# Sheet1.net
KiCad netlist of a schematic drawn in Altium Designer
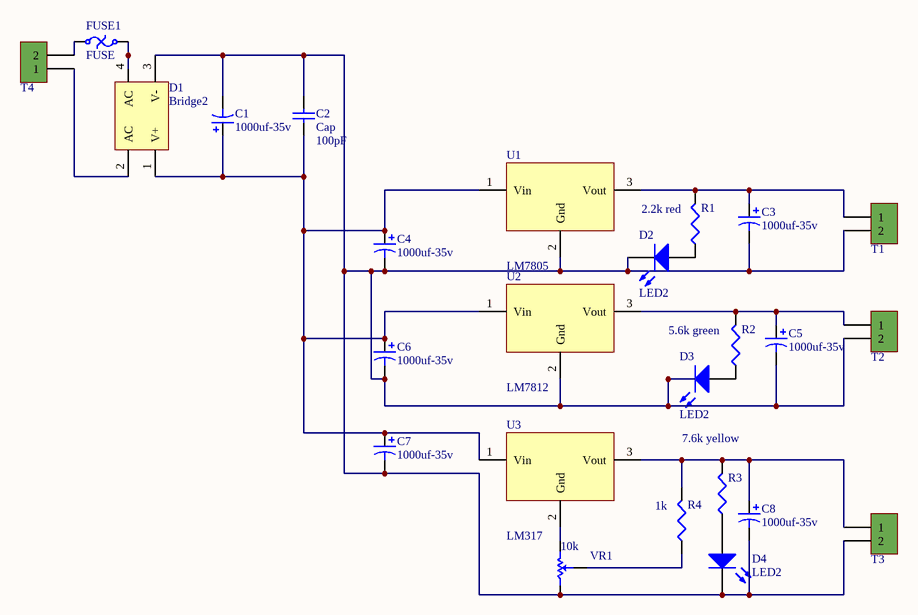
[diagram p0: Sheet1.SchDoc]

(export (version "E")
  (design (tool "Eeschema 10.0.6"))
  (components
    (comp (ref "C1")
      (value "1000uf-35v")
      (footprint "RB7.6-15")
      (description "Polarized Capacitor (Radial)")
      (fields (field (name "PUBLISHER") "Altium Limited"))
      (libsource (lib "Miscellaneous Devices") (part "Cap Pol1"))
    )
    (comp (ref "C2")
      (value "Cap")
      (footprint "RAD-0.3")
      (description "Capacitor")
      (fields (field (name "ALTIUM_VALUE") "100pF") (field (name "PUBLISHER") "Altium Limited"))
      (libsource (lib "Miscellaneous Devices") (part "Cap"))
    )
    (comp (ref "C3")
      (value "1000uf-35v")
      (footprint "RB7.6-15")
      (description "Polarized Capacitor (Radial)")
      (fields (field (name "PUBLISHER") "Altium Limited"))
      (libsource (lib "Miscellaneous Devices") (part "Cap Pol1"))
    )
    (comp (ref "C4")
      (value "1000uf-35v")
      (footprint "RB7.6-15")
      (description "Polarized Capacitor (Radial)")
      (fields (field (name "PUBLISHER") "Altium Limited"))
      (libsource (lib "Miscellaneous Devices") (part "Cap Pol1"))
    )
    (comp (ref "C5")
      (value "1000uf-35v")
      (footprint "RB7.6-15")
      (description "Polarized Capacitor (Radial)")
      (fields (field (name "PUBLISHER") "Altium Limited"))
      (libsource (lib "Miscellaneous Devices") (part "Cap Pol1"))
    )
    (comp (ref "C6")
      (value "1000uf-35v")
      (footprint "RB7.6-15")
      (description "Polarized Capacitor (Radial)")
      (fields (field (name "PUBLISHER") "Altium Limited"))
      (libsource (lib "Miscellaneous Devices") (part "Cap Pol1"))
    )
    (comp (ref "C7")
      (value "1000uf-35v")
      (footprint "RB7.6-15")
      (description "Polarized Capacitor (Radial)")
      (fields (field (name "PUBLISHER") "Altium Limited"))
      (libsource (lib "Miscellaneous Devices") (part "Cap Pol1"))
    )
    (comp (ref "C8")
      (value "1000uf-35v")
      (footprint "RB7.6-15")
      (description "Polarized Capacitor (Radial)")
      (fields (field (name "PUBLISHER") "Altium Limited"))
      (libsource (lib "Miscellaneous Devices") (part "Cap Pol1"))
    )
    (comp (ref "D1")
      (value "Bridge2")
      (footprint "D-46_6A")
      (description "Diode Bridge")
      (fields (field (name "PUBLISHER") "Altium Limited"))
      (libsource (lib "Miscellaneous Devices") (part "Bridge2"))
    )
    (comp (ref "D2")
      (value "LED2")
      (footprint "3.2X1.6X1.1")
      (description "Typical RED, GREEN, YELLOW, AMBER GaAs LED")
      (fields (field (name "PUBLISHER") "Altium Limited"))
      (libsource (lib "Miscellaneous Devices") (part "LED2"))
    )
    (comp (ref "D3")
      (value "LED2")
      (footprint "3.2X1.6X1.1")
      (description "Typical RED, GREEN, YELLOW, AMBER GaAs LED")
      (fields (field (name "PUBLISHER") "Altium Limited"))
      (libsource (lib "Miscellaneous Devices") (part "LED2"))
    )
    (comp (ref "D4")
      (value "LED2")
      (footprint "3.2X1.6X1.1")
      (description "Typical RED, GREEN, YELLOW, AMBER GaAs LED")
      (fields (field (name "PUBLISHER") "Altium Limited"))
      (libsource (lib "Miscellaneous Devices") (part "LED2"))
    )
    (comp (ref "FUSE1") (value "FUSE") (footprint "1206_F") (libsource (lib "Fuse") (part "FUSE SMD")))
    (comp (ref "R1")
      (value "2.2k red")
      (footprint "1206_R")
      (description "SMD Resistor")
      (fields (field (name "TOLERANCE") "[1%]"))
      (libsource (lib "Resistor") (part "Resistor SMD"))
    )
    (comp (ref "R2")
      (value "5.6k green")
      (footprint "1206_R")
      (description "SMD Resistor")
      (fields (field (name "TOLERANCE") "[1%]"))
      (libsource (lib "Resistor") (part "Resistor SMD"))
    )
    (comp (ref "R3")
      (value "7.6k yellow")
      (footprint "1206_R")
      (description "SMD Resistor")
      (fields (field (name "TOLERANCE") "[1%]"))
      (libsource (lib "Resistor") (part "Resistor SMD"))
    )
    (comp (ref "R4")
      (value "1k")
      (footprint "1206_R")
      (description "SMD Resistor")
      (fields (field (name "TOLERANCE") "[1%]"))
      (libsource (lib "Resistor") (part "Resistor SMD"))
    )
    (comp (ref "T1")
      (value "Phoenix 2 Pin")
      (footprint "Phoenix_2PIN_RA_P7.62mm")
      (libsource (lib "Connector") (part "Phoenix 2 Pin"))
    )
    (comp (ref "T2")
      (value "Phoenix 2 Pin")
      (footprint "Phoenix_2PIN_RA_P7.62mm")
      (libsource (lib "Connector") (part "Phoenix 2 Pin"))
    )
    (comp (ref "T3")
      (value "Phoenix 2 Pin")
      (footprint "Phoenix_2PIN_RA_P7.62mm")
      (libsource (lib "Connector") (part "Phoenix 2 Pin"))
    )
    (comp (ref "T4")
      (value "Phoenix 2 Pin")
      (footprint "Phoenix_2PIN_RA_P7.62mm")
      (libsource (lib "") (part "Phoenix 2 Pin_1"))
    )
    (comp (ref "U1")
      (value "LM7805")
      (footprint "LM78XXCT_HEATSINK")
      (description "LM78XX")
      (libsource (lib "Regulator") (part "LM78XX"))
    )
    (comp (ref "U2")
      (value "LM7812")
      (footprint "LM78XXCT_HEATSINK")
      (description "LM78XX")
      (libsource (lib "Regulator") (part "LM78XX"))
    )
    (comp (ref "U3")
      (value "LM317")
      (footprint "LM78XXCT_HEATSINK")
      (description "LM78XX")
      (libsource (lib "Regulator") (part "LM78XX"))
    )
    (comp (ref "VR1")
      (value "10k")
      (footprint "POT_WH148")
      (description "Variable Resistor")
      (libsource (lib "Resistor") (part "Pot Res Var"))
    )
  )
  (nets
    (net (code "1") (name "Net-(D1-AC-Pad2)") (class "Default")
      (node (ref "D1") (pin "2") (pinfunction "AC_2") (pintype "passive"))
      (node (ref "T4") (pin "1") (pinfunction "1_1") (pintype "passive"))
    )
    (net (code "2") (name "Net-(D1-AC-Pad4)") (class "Default")
      (node (ref "D1") (pin "4") (pinfunction "AC_4") (pintype "passive"))
      (node (ref "FUSE1") (pin "2") (pinfunction "2_2") (pintype "passive"))
    )
    (net (code "3") (name "Net-(D1-V+)") (class "Default")
      (node (ref "C1") (pin "1") (pinfunction "1_1") (pintype "passive"))
      (node (ref "C2") (pin "1") (pinfunction "1_1") (pintype "passive"))
      (node (ref "C4") (pin "1") (pinfunction "1_1") (pintype "passive"))
      (node (ref "C6") (pin "1") (pinfunction "1_1") (pintype "passive"))
      (node (ref "C7") (pin "1") (pinfunction "1_1") (pintype "passive"))
      (node (ref "D1") (pin "1") (pinfunction "V+_1") (pintype "passive"))
      (node (ref "U1") (pin "1") (pinfunction "Vin_1") (pintype "passive"))
      (node (ref "U2") (pin "1") (pinfunction "Vin_1") (pintype "passive"))
      (node (ref "U3") (pin "1") (pinfunction "Vin_1") (pintype "passive"))
    )
    (net (code "4") (name "Net-(D1-V-)") (class "Default")
      (node (ref "C1") (pin "2") (pinfunction "2_2") (pintype "passive"))
      (node (ref "C2") (pin "2") (pinfunction "2_2") (pintype "passive"))
      (node (ref "C3") (pin "2") (pinfunction "2_2") (pintype "passive"))
      (node (ref "C4") (pin "2") (pinfunction "2_2") (pintype "passive"))
      (node (ref "C5") (pin "2") (pinfunction "2_2") (pintype "passive"))
      (node (ref "C6") (pin "2") (pinfunction "2_2") (pintype "passive"))
      (node (ref "C7") (pin "2") (pinfunction "2_2") (pintype "passive"))
      (node (ref "C8") (pin "2") (pinfunction "2_2") (pintype "passive"))
      (node (ref "D1") (pin "3") (pinfunction "V-_3") (pintype "passive"))
      (node (ref "D2") (pin "2") (pinfunction "K_2") (pintype "passive"))
      (node (ref "D3") (pin "2") (pinfunction "K_2") (pintype "passive"))
      (node (ref "D4") (pin "2") (pinfunction "K_2") (pintype "passive"))
      (node (ref "T1") (pin "2") (pinfunction "2_2") (pintype "passive"))
      (node (ref "T2") (pin "2") (pinfunction "2_2") (pintype "passive"))
      (node (ref "T3") (pin "2") (pinfunction "2_2") (pintype "passive"))
      (node (ref "U1") (pin "2") (pinfunction "Gnd_2") (pintype "passive"))
      (node (ref "U2") (pin "2") (pinfunction "Gnd_2") (pintype "passive"))
      (node (ref "VR1") (pin "1") (pinfunction "CCW_1") (pintype "passive"))
    )
    (net (code "5") (name "Net-(D2-A)") (class "Default")
      (node (ref "D2") (pin "1") (pinfunction "A_1") (pintype "passive"))
      (node (ref "R1") (pin "1") (pinfunction "R1_1") (pintype "passive"))
    )
    (net (code "6") (name "Net-(D3-A)") (class "Default")
      (node (ref "D3") (pin "1") (pinfunction "A_1") (pintype "passive"))
      (node (ref "R2") (pin "1") (pinfunction "R1_1") (pintype "passive"))
    )
    (net (code "7") (name "Net-(D4-A)") (class "Default")
      (node (ref "D4") (pin "1") (pinfunction "A_1") (pintype "passive"))
      (node (ref "R3") (pin "1") (pinfunction "R1_1") (pintype "passive"))
    )
    (net (code "8") (name "Net-(FUSE1-Pad1)") (class "Default")
      (node (ref "FUSE1") (pin "1") (pinfunction "1_1") (pintype "passive"))
      (node (ref "T4") (pin "2") (pinfunction "2_2") (pintype "passive"))
    )
    (net (code "9") (name "Net-(R1-R2)") (class "Default")
      (node (ref "C3") (pin "1") (pinfunction "1_1") (pintype "passive"))
      (node (ref "R1") (pin "2") (pinfunction "R2_2") (pintype "passive"))
      (node (ref "T1") (pin "1") (pinfunction "1_1") (pintype "passive"))
      (node (ref "U1") (pin "3") (pinfunction "Vout_3") (pintype "passive"))
    )
    (net (code "10") (name "Net-(R2-R2)") (class "Default")
      (node (ref "C5") (pin "1") (pinfunction "1_1") (pintype "passive"))
      (node (ref "R2") (pin "2") (pinfunction "R2_2") (pintype "passive"))
      (node (ref "T2") (pin "1") (pinfunction "1_1") (pintype "passive"))
      (node (ref "U2") (pin "3") (pinfunction "Vout_3") (pintype "passive"))
    )
    (net (code "11") (name "Net-(R3-R2)") (class "Default")
      (node (ref "C8") (pin "1") (pinfunction "1_1") (pintype "passive"))
      (node (ref "R3") (pin "2") (pinfunction "R2_2") (pintype "passive"))
      (node (ref "R4") (pin "2") (pinfunction "R2_2") (pintype "passive"))
      (node (ref "T3") (pin "1") (pinfunction "1_1") (pintype "passive"))
      (node (ref "U3") (pin "3") (pinfunction "Vout_3") (pintype "passive"))
    )
    (net (code "12") (name "Net-(R4-R1)") (class "Default")
      (node (ref "R4") (pin "1") (pinfunction "R1_1") (pintype "passive"))
      (node (ref "VR1") (pin "3") (pinfunction "Setpoint_3") (pintype "passive"))
    )
    (net (code "13") (name "Net-(U3-Gnd)") (class "Default")
      (node (ref "U3") (pin "2") (pinfunction "Gnd_2") (pintype "passive"))
      (node (ref "VR1") (pin "2") (pinfunction "CW_2") (pintype "passive"))
    )
  )
)
